# minishell.net
KiCad netlist of a schematic drawn in EAGLE
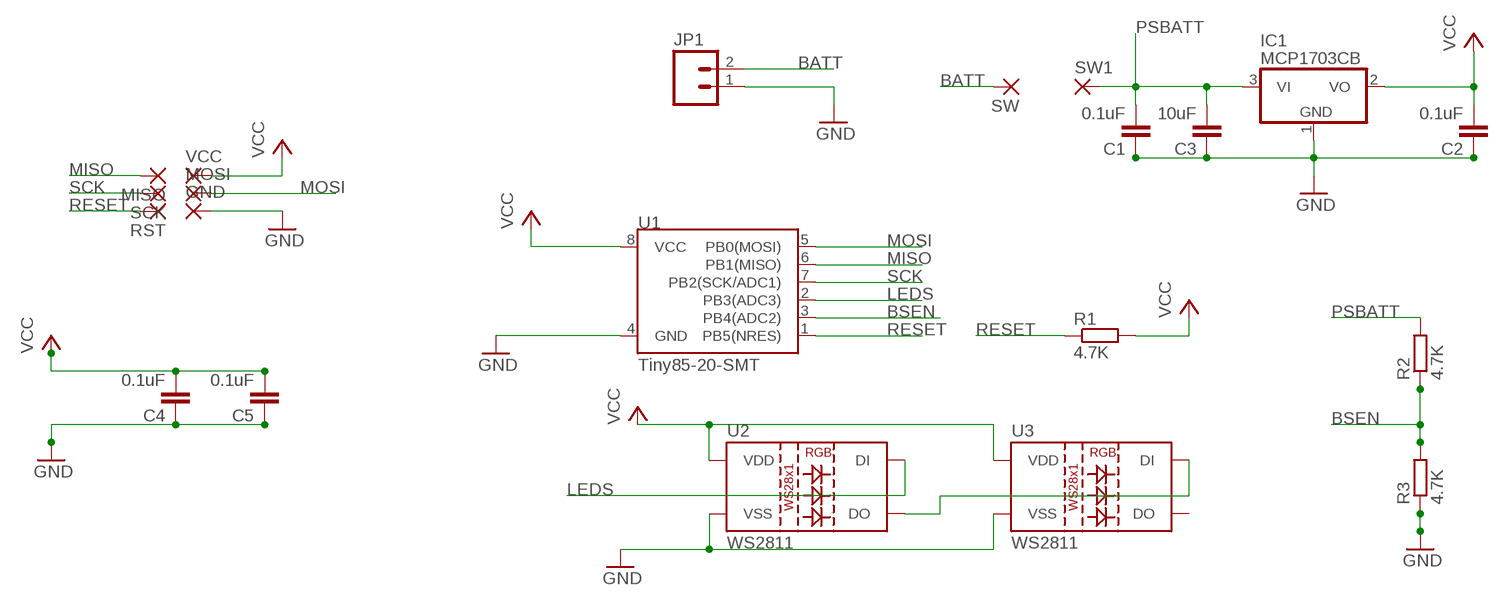
[diagram p0: schematic, sheet 1]

(export (version "E")
  (design (tool "Eeschema 10.0.6"))
  (components
    (comp (ref "C1")
      (value "0.1uF")
      (footprint "eagle-import:C0603")
      (libsource (lib "eagle-import") (part "C-EUC0603"))
    )
    (comp (ref "C2")
      (value "0.1uF")
      (footprint "eagle-import:C0603")
      (libsource (lib "eagle-import") (part "C-EUC0603"))
    )
    (comp (ref "C3")
      (value "10uF")
      (footprint "eagle-import:C0805")
      (libsource (lib "eagle-import") (part "C-EUC0805"))
    )
    (comp (ref "C4")
      (value "0.1uF")
      (footprint "eagle-import:C0603")
      (libsource (lib "eagle-import") (part "C-EUC0603"))
    )
    (comp (ref "C5")
      (value "0.1uF")
      (footprint "eagle-import:C0603")
      (libsource (lib "eagle-import") (part "C-EUC0603"))
    )
    (comp (ref "GND")
      (value "SMD2")
      (footprint "eagle-import:SMD1,27-2,54")
      (libsource (lib "eagle-import") (part "SMD2"))
    )
    (comp (ref "IC1")
      (value "MCP1703CB")
      (footprint "eagle-import:SOT23")
      (libsource (lib "eagle-import") (part "MCP1703CB"))
    )
    (comp (ref "JP1")
      (value "M02PTH")
      (footprint "eagle-import:1X02")
      (libsource (lib "eagle-import") (part "M02PTH"))
    )
    (comp (ref "MISO")
      (value "SMD2")
      (footprint "eagle-import:SMD1,27-2,54")
      (libsource (lib "eagle-import") (part "SMD2"))
    )
    (comp (ref "MOSI")
      (value "SMD2")
      (footprint "eagle-import:SMD1,27-2,54")
      (libsource (lib "eagle-import") (part "SMD2"))
    )
    (comp (ref "R1")
      (value "4.7K")
      (footprint "eagle-import:R0603")
      (libsource (lib "eagle-import") (part "R-EU_R0603"))
    )
    (comp (ref "R2")
      (value "4.7K")
      (footprint "eagle-import:R0603")
      (libsource (lib "eagle-import") (part "R-EU_R0603"))
    )
    (comp (ref "R3")
      (value "4.7K")
      (footprint "eagle-import:R0603")
      (libsource (lib "eagle-import") (part "R-EU_R0603"))
    )
    (comp (ref "RST")
      (value "SMD2")
      (footprint "eagle-import:SMD1,27-2,54")
      (libsource (lib "eagle-import") (part "SMD2"))
    )
    (comp (ref "SCK")
      (value "SMD2")
      (footprint "eagle-import:SMD1,27-2,54")
      (libsource (lib "eagle-import") (part "SMD2"))
    )
    (comp (ref "SW")
      (value "SMD2")
      (footprint "eagle-import:SMD1,27-2,54")
      (libsource (lib "eagle-import") (part "SMD2"))
    )
    (comp (ref "SW1")
      (value "SMD2")
      (footprint "eagle-import:SMD1,27-2,54")
      (libsource (lib "eagle-import") (part "SMD2"))
    )
    (comp (ref "U1")
      (value "Tiny85-20-SMT")
      (footprint "eagle-import:SO08-EIAJ")
      (libsource (lib "eagle-import") (part "ATTINY45TINY85-20-SMT"))
    )
    (comp (ref "U2")
      (value "WS2811")
      (footprint "eagle-import:LED-TRICOLOR-5050-IC")
      (libsource (lib "eagle-import") (part "LED-TRICOLOR-5050-ICWS2811"))
    )
    (comp (ref "U3")
      (value "WS2811")
      (footprint "eagle-import:LED-TRICOLOR-5050-IC")
      (libsource (lib "eagle-import") (part "LED-TRICOLOR-5050-ICWS2811"))
    )
    (comp (ref "VCC")
      (value "SMD2")
      (footprint "eagle-import:SMD1,27-2,54")
      (libsource (lib "eagle-import") (part "SMD2"))
    )
  )
  (nets
    (net (code "1") (name "/BATT") (class "Default")
      (node (ref "JP1") (pin "2") (pinfunction "2_2") (pintype "passive"))
      (node (ref "SW") (pin "1") (pinfunction "P_1") (pintype "passive"))
    )
    (net (code "2") (name "/BSEN") (class "Default")
      (node (ref "R2") (pin "1") (pinfunction "1_1") (pintype "passive"))
      (node (ref "R3") (pin "2") (pinfunction "2_2") (pintype "passive"))
      (node (ref "U1") (pin "3") (pinfunction "PB4(ADC2)_3") (pintype "bidirectional"))
    )
    (net (code "3") (name "/LEDS") (class "Default")
      (node (ref "U1") (pin "2") (pinfunction "PB3(ADC3)_2") (pintype "bidirectional"))
      (node (ref "U2") (pin "2") (pinfunction "DI_2") (pintype "bidirectional"))
    )
    (net (code "4") (name "/MISO") (class "Default")
      (node (ref "MISO") (pin "1") (pinfunction "P_1") (pintype "passive"))
      (node (ref "U1") (pin "6") (pinfunction "PB1(MISO)_6") (pintype "bidirectional"))
    )
    (net (code "5") (name "/MOSI") (class "Default")
      (node (ref "MOSI") (pin "1") (pinfunction "P_1") (pintype "passive"))
      (node (ref "U1") (pin "5") (pinfunction "PB0(MOSI)_5") (pintype "bidirectional"))
    )
    (net (code "6") (name "/PSBATT") (class "Default")
      (node (ref "C1") (pin "2") (pinfunction "2_2") (pintype "passive"))
      (node (ref "C3") (pin "2") (pinfunction "2_2") (pintype "passive"))
      (node (ref "IC1") (pin "3") (pinfunction "VI_3") (pintype "input"))
      (node (ref "R2") (pin "2") (pinfunction "2_2") (pintype "passive"))
      (node (ref "SW1") (pin "1") (pinfunction "P_1") (pintype "passive"))
    )
    (net (code "7") (name "/RESET") (class "Default")
      (node (ref "R1") (pin "1") (pinfunction "1_1") (pintype "passive"))
      (node (ref "RST") (pin "1") (pinfunction "P_1") (pintype "passive"))
      (node (ref "U1") (pin "1") (pinfunction "PB5(NRES)_1") (pintype "bidirectional"))
    )
    (net (code "8") (name "/SCK") (class "Default")
      (node (ref "SCK") (pin "1") (pinfunction "P_1") (pintype "passive"))
      (node (ref "U1") (pin "7") (pinfunction "PB2(SCK/ADC1)_7") (pintype "bidirectional"))
    )
    (net (code "9") (name "GND") (class "Default")
      (node (ref "C1") (pin "1") (pinfunction "1_1") (pintype "passive"))
      (node (ref "C2") (pin "1") (pinfunction "1_1") (pintype "passive"))
      (node (ref "C3") (pin "1") (pinfunction "1_1") (pintype "passive"))
      (node (ref "C4") (pin "1") (pinfunction "1_1") (pintype "passive"))
      (node (ref "C5") (pin "1") (pinfunction "1_1") (pintype "passive"))
      (node (ref "GND") (pin "1") (pinfunction "P_1") (pintype "passive"))
      (node (ref "IC1") (pin "1") (pinfunction "GND_1") (pintype "passive"))
      (node (ref "JP1") (pin "1") (pinfunction "1_1") (pintype "passive"))
      (node (ref "R3") (pin "1") (pinfunction "1_1") (pintype "passive"))
      (node (ref "U1") (pin "4") (pinfunction "GND_4") (pintype "bidirectional"))
      (node (ref "U2") (pin "6") (pinfunction "VSS_6") (pintype "bidirectional"))
      (node (ref "U3") (pin "6") (pinfunction "VSS_6") (pintype "bidirectional"))
    )
    (net (code "10") (name "Net-(U2-DO)") (class "Default")
      (node (ref "U2") (pin "1") (pinfunction "DO_1") (pintype "bidirectional"))
      (node (ref "U3") (pin "2") (pinfunction "DI_2") (pintype "bidirectional"))
    )
    (net (code "11") (name "VCC") (class "Default")
      (node (ref "C2") (pin "2") (pinfunction "2_2") (pintype "passive"))
      (node (ref "C4") (pin "2") (pinfunction "2_2") (pintype "passive"))
      (node (ref "C5") (pin "2") (pinfunction "2_2") (pintype "passive"))
      (node (ref "IC1") (pin "2") (pinfunction "VO_2") (pintype "passive"))
      (node (ref "R1") (pin "2") (pinfunction "2_2") (pintype "passive"))
      (node (ref "U1") (pin "8") (pinfunction "VCC_8") (pintype "bidirectional"))
      (node (ref "U2") (pin "3") (pinfunction "VDD_3") (pintype "bidirectional"))
      (node (ref "U2") (pin "5") (pinfunction "VDD_5") (pintype "bidirectional"))
      (node (ref "U3") (pin "3") (pinfunction "VDD_3") (pintype "bidirectional"))
      (node (ref "U3") (pin "5") (pinfunction "VDD_5") (pintype "bidirectional"))
      (node (ref "VCC") (pin "1") (pinfunction "P_1") (pintype "passive"))
    )
    (net (code "12") (name "unconnected-(U3-DO-Pad1)") (class "Default")
      (node (ref "U3") (pin "1") (pinfunction "DO_1") (pintype "bidirectional"))
    )
  )
)
